# PCB_PUMP_ATTINY.net
KiCad netlist of a schematic drawn in EAGLE
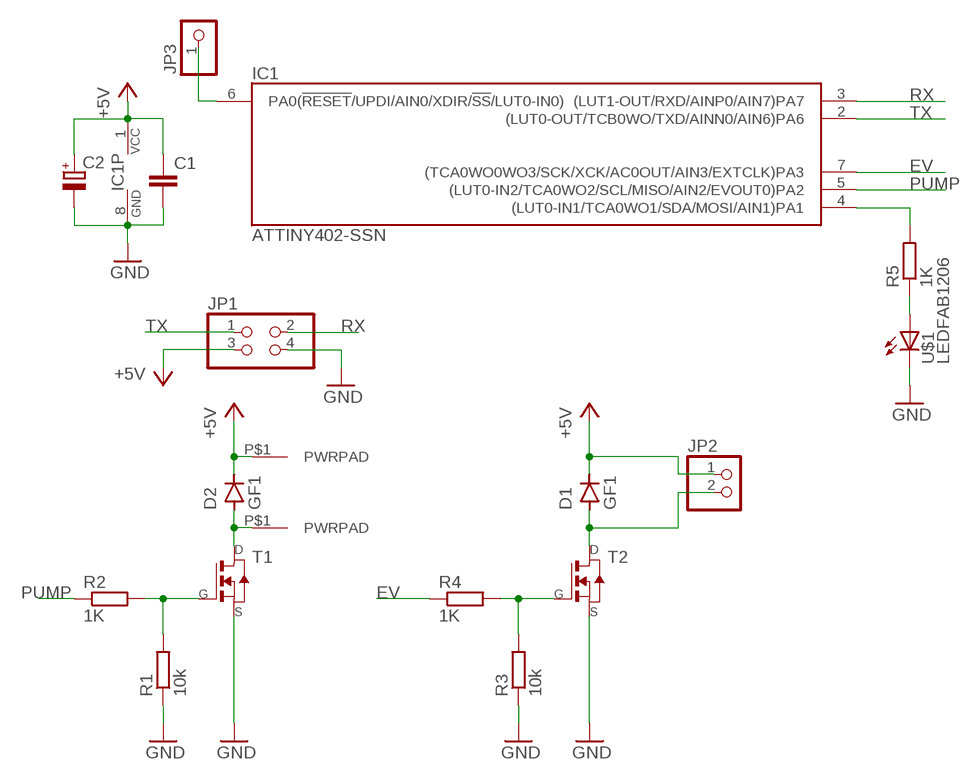
[diagram p0: schematic, sheet 1]

(export (version "E")
  (design (tool "Eeschema 10.0.6"))
  (components
    (comp (ref "C1")
      (value "C-EUC1206")
      (footprint "eagle-import:C1206")
      (libsource (lib "eagle-import") (part "C-EUC1206"))
    )
    (comp (ref "C2")
      (value "CPOL-EU153CLV-0505")
      (footprint "eagle-import:153CLV-0505")
      (libsource (lib "eagle-import") (part "CPOL-EU153CLV-0505"))
    )
    (comp (ref "D1")
      (value "GF1")
      (footprint "eagle-import:SMA-DO214AC")
      (libsource (lib "eagle-import") (part "GF1"))
    )
    (comp (ref "D2")
      (value "GF1")
      (footprint "eagle-import:SMA-DO214AC")
      (libsource (lib "eagle-import") (part "GF1"))
    )
    (comp (ref "IC1")
      (value "ATTINY402-SSN")
      (footprint "eagle-import:SO8")
      (libsource (lib "eagle-import") (part "ATTINY02-SSN4"))
    )
    (comp (ref "J3")
      (value "PWRPAD2-5MM")
      (footprint "eagle-import:PWRPAD_2-5MM")
      (libsource (lib "eagle-import") (part "PWRPAD2-5MM"))
    )
    (comp (ref "J4")
      (value "PWRPAD2-5MM")
      (footprint "eagle-import:PWRPAD_2-5MM")
      (libsource (lib "eagle-import") (part "PWRPAD2-5MM"))
    )
    (comp (ref "JP1")
      (value "PINHD-2X02_2.54-SMD")
      (footprint "eagle-import:2X02SMD")
      (libsource (lib "eagle-import") (part "PINHD-2X02_2.54-SMD"))
    )
    (comp (ref "JP2")
      (value "PINHD-1X02_2.54-SMD-90°")
      (footprint "eagle-import:1X02SMD_90")
      (libsource (lib "eagle-import") (part "PINHD-1X02_2.54-SMD-90°"))
    )
    (comp (ref "JP3")
      (value "PINHD-1X01_2.54-SMD")
      (footprint "eagle-import:1X01SMD")
      (libsource (lib "eagle-import") (part "PINHD-1X01_2.54-SMD"))
    )
    (comp (ref "R1")
      (value "10k")
      (footprint "eagle-import:R1206")
      (libsource (lib "eagle-import") (part "R-EU_R1206"))
    )
    (comp (ref "R2")
      (value "1K")
      (footprint "eagle-import:R1206")
      (libsource (lib "eagle-import") (part "R-EU_R1206"))
    )
    (comp (ref "R3")
      (value "10k")
      (footprint "eagle-import:R1206")
      (libsource (lib "eagle-import") (part "R-EU_R1206"))
    )
    (comp (ref "R4")
      (value "1K")
      (footprint "eagle-import:R1206")
      (libsource (lib "eagle-import") (part "R-EU_R1206"))
    )
    (comp (ref "R5")
      (value "1K")
      (footprint "eagle-import:R1206")
      (libsource (lib "eagle-import") (part "R-EU_R1206"))
    )
    (comp (ref "T1")
      (value "NMOSFETSOT23")
      (footprint "eagle-import:SOT-23")
      (libsource (lib "eagle-import") (part "NMOSFETSOT23"))
    )
    (comp (ref "T2")
      (value "NMOSFETSOT23")
      (footprint "eagle-import:SOT-23")
      (libsource (lib "eagle-import") (part "NMOSFETSOT23"))
    )
    (comp (ref "U$1")
      (value "LEDFAB1206")
      (footprint "eagle-import:LED1206FAB")
      (libsource (lib "eagle-import") (part "LEDFAB1206"))
    )
  )
  (nets
    (net (code "1") (name "+5V") (class "Default")
      (node (ref "C1") (pin "1") (pinfunction "1_1") (pintype "passive"))
      (node (ref "C2") (pin "+") (pinfunction "+_+") (pintype "passive"))
      (node (ref "D1") (pin "K") (pinfunction "C_K") (pintype "passive"))
      (node (ref "D2") (pin "K") (pinfunction "C_K") (pintype "passive"))
      (node (ref "IC1") (pin "1") (pinfunction "VCC_1") (pintype "power_in"))
      (node (ref "J4") (pin "P$1") (pinfunction "PWRPAD_P$1") (pintype "bidirectional"))
      (node (ref "JP1") (pin "3") (pinfunction "3_3") (pintype "passive"))
      (node (ref "JP2") (pin "1") (pinfunction "1_1") (pintype "passive"))
    )
    (net (code "2") (name "/EV") (class "Default")
      (node (ref "IC1") (pin "7") (pinfunction "(TCA0WO0WO3/SCK/XCK/AC0OUT/AIN3/EXTCLK)PA3_7") (pintype "bidirectional"))
      (node (ref "R4") (pin "1") (pinfunction "1_1") (pintype "passive"))
    )
    (net (code "3") (name "/PUMP") (class "Default")
      (node (ref "IC1") (pin "5") (pinfunction "(LUT0-IN2/TCA0WO2/SCL/MISO/AIN2/EVOUT0)PA2_5") (pintype "bidirectional"))
      (node (ref "R2") (pin "1") (pinfunction "1_1") (pintype "passive"))
    )
    (net (code "4") (name "/RX") (class "Default")
      (node (ref "IC1") (pin "3") (pinfunction "(LUT1-OUT/RXD/AINP0/AIN7)PA7_3") (pintype "bidirectional"))
      (node (ref "JP1") (pin "2") (pinfunction "2_2") (pintype "passive"))
    )
    (net (code "5") (name "/TX") (class "Default")
      (node (ref "IC1") (pin "2") (pinfunction "(LUT0-OUT/TCB0WO/TXD/AINN0/AIN6)PA6_2") (pintype "bidirectional"))
      (node (ref "JP1") (pin "1") (pinfunction "1_1") (pintype "passive"))
    )
    (net (code "6") (name "GND") (class "Default")
      (node (ref "C1") (pin "2") (pinfunction "2_2") (pintype "passive"))
      (node (ref "C2") (pin "-") (pinfunction "-_-") (pintype "passive"))
      (node (ref "IC1") (pin "8") (pinfunction "GND_8") (pintype "power_in"))
      (node (ref "JP1") (pin "4") (pinfunction "4_4") (pintype "passive"))
      (node (ref "R1") (pin "1") (pinfunction "1_1") (pintype "passive"))
      (node (ref "R3") (pin "1") (pinfunction "1_1") (pintype "passive"))
      (node (ref "T1") (pin "2") (pinfunction "S_2") (pintype "passive"))
      (node (ref "T2") (pin "2") (pinfunction "S_2") (pintype "passive"))
      (node (ref "U$1") (pin "2") (pinfunction "C_2") (pintype "passive"))
    )
    (net (code "7") (name "Net-(IC1A-(LUT0-IN1{slash}TCA0WO1{slash}SDA{slash}MOSI{slash}AIN1)PA1)") (class "Default")
      (node (ref "IC1") (pin "4") (pinfunction "(LUT0-IN1/TCA0WO1/SDA/MOSI/AIN1)PA1_4") (pintype "bidirectional"))
      (node (ref "R5") (pin "2") (pinfunction "2_2") (pintype "passive"))
    )
    (net (code "8") (name "Net-(IC1A-PA0(~{RESET}{slash}UPDI{slash}AIN0{slash}XDIR{slash}~{SS}{slash}LUT0-IN0))") (class "Default")
      (node (ref "IC1") (pin "6") (pinfunction "PA0(~{RESET}/UPDI/AIN0/XDIR/~{SS}/LUT0-IN0)_6") (pintype "bidirectional"))
      (node (ref "JP3") (pin "1") (pinfunction "1_1") (pintype "passive"))
    )
    (net (code "9") (name "Net-(J3-PWRPAD)") (class "Default")
      (node (ref "D2") (pin "A") (pinfunction "A_A") (pintype "passive"))
      (node (ref "J3") (pin "P$1") (pinfunction "PWRPAD_P$1") (pintype "bidirectional"))
      (node (ref "T1") (pin "1") (pinfunction "D_1") (pintype "passive"))
    )
    (net (code "10") (name "Net-(T1-G)") (class "Default")
      (node (ref "R1") (pin "2") (pinfunction "2_2") (pintype "passive"))
      (node (ref "R2") (pin "2") (pinfunction "2_2") (pintype "passive"))
      (node (ref "T1") (pin "3") (pinfunction "G_3") (pintype "passive"))
    )
    (net (code "11") (name "Net-(T2-D)") (class "Default")
      (node (ref "D1") (pin "A") (pinfunction "A_A") (pintype "passive"))
      (node (ref "JP2") (pin "2") (pinfunction "2_2") (pintype "passive"))
      (node (ref "T2") (pin "1") (pinfunction "D_1") (pintype "passive"))
    )
    (net (code "12") (name "Net-(T2-G)") (class "Default")
      (node (ref "R3") (pin "2") (pinfunction "2_2") (pintype "passive"))
      (node (ref "R4") (pin "2") (pinfunction "2_2") (pintype "passive"))
      (node (ref "T2") (pin "3") (pinfunction "G_3") (pintype "passive"))
    )
    (net (code "13") (name "Net-(U$1-A)") (class "Default")
      (node (ref "R5") (pin "1") (pinfunction "1_1") (pintype "passive"))
      (node (ref "U$1") (pin "1") (pinfunction "A_1") (pintype "passive"))
    )
  )
)
